# MRF49XA--0805_Mod.net
KiCad netlist of a schematic drawn in EAGLE
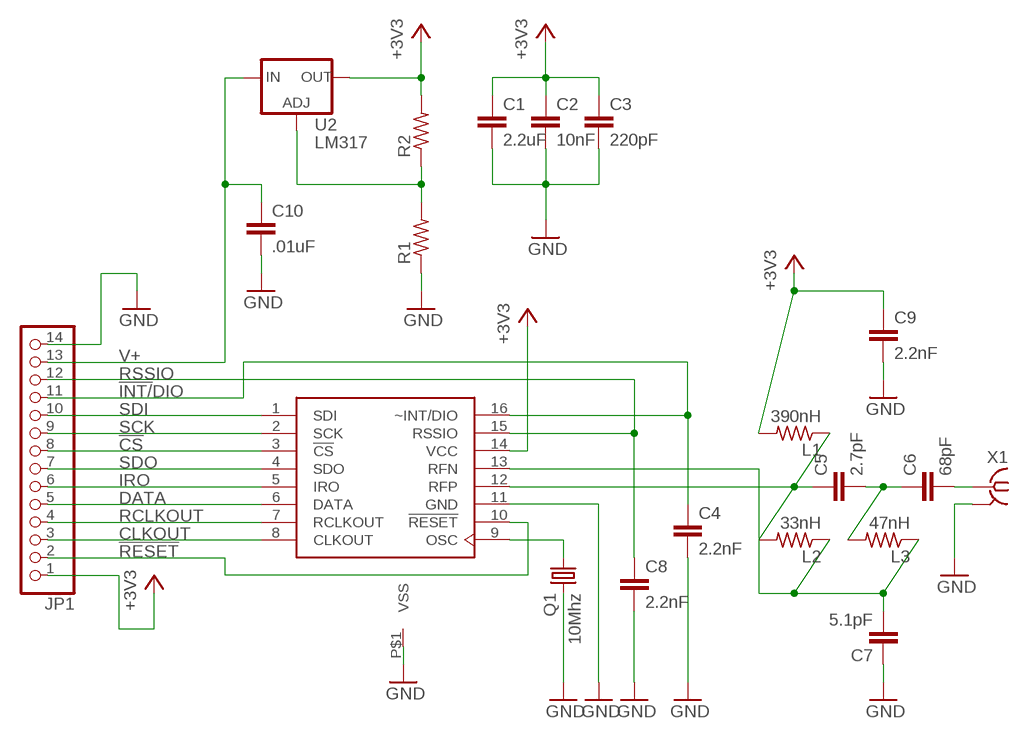
[diagram p0: schematic, sheet 1]

(export (version "E")
  (design (tool "Eeschema 10.0.6"))
  (components
    (comp (ref "C1")
      (value "2.2uF")
      (footprint "eagle-import:C0805")
      (libsource (lib "eagle-import") (part "C-EUC0805"))
    )
    (comp (ref "C2")
      (value "10nF")
      (footprint "eagle-import:C0805")
      (libsource (lib "eagle-import") (part "C-EUC0805"))
    )
    (comp (ref "C3")
      (value "220pF")
      (footprint "eagle-import:C0805")
      (libsource (lib "eagle-import") (part "C-EUC0805"))
    )
    (comp (ref "C4")
      (value "2.2nF")
      (footprint "eagle-import:C0805")
      (libsource (lib "eagle-import") (part "C-EUC0805"))
    )
    (comp (ref "C5")
      (value "2.7pF")
      (footprint "eagle-import:C0805")
      (libsource (lib "eagle-import") (part "C-EUC0805"))
    )
    (comp (ref "C6")
      (value "68pF")
      (footprint "eagle-import:C0805")
      (libsource (lib "eagle-import") (part "C-EUC0805"))
    )
    (comp (ref "C7")
      (value "5.1pF")
      (footprint "eagle-import:C0805")
      (libsource (lib "eagle-import") (part "C-EUC0805"))
    )
    (comp (ref "C8")
      (value "2.2nF")
      (footprint "eagle-import:C0805")
      (libsource (lib "eagle-import") (part "C-EUC0805"))
    )
    (comp (ref "C9")
      (value "2.2nF")
      (footprint "eagle-import:C0805")
      (libsource (lib "eagle-import") (part "C-EUC0805"))
    )
    (comp (ref "C10")
      (value ".01uF")
      (footprint "eagle-import:C0805")
      (libsource (lib "eagle-import") (part "C-EUC0805"))
    )
    (comp (ref "JP1")
      (value "PINHD-1X14")
      (footprint "eagle-import:1X14")
      (libsource (lib "eagle-import") (part "PINHD-1X14"))
    )
    (comp (ref "L1")
      (value "390nH")
      (footprint "eagle-import:R0805")
      (libsource (lib "eagle-import") (part "resistor_R-US_R0805"))
    )
    (comp (ref "L2")
      (value "33nH")
      (footprint "eagle-import:R0805")
      (libsource (lib "eagle-import") (part "resistor_R-US_R0805"))
    )
    (comp (ref "L3")
      (value "47nH")
      (footprint "eagle-import:R0805")
      (libsource (lib "eagle-import") (part "resistor_R-US_R0805"))
    )
    (comp (ref "Q1")
      (value "10Mhz")
      (footprint "eagle-import:CTS406")
      (libsource (lib "eagle-import") (part "CRYSTALCTS406"))
    )
    (comp (ref "R1")
      (value "R-US_M0805")
      (footprint "eagle-import:M0805")
      (libsource (lib "eagle-import") (part "R-US_M0805"))
    )
    (comp (ref "R2")
      (value "R-US_M0805")
      (footprint "eagle-import:M0805")
      (libsource (lib "eagle-import") (part "R-US_M0805"))
    )
    (comp (ref "U$1")
      (value "MRF49XA")
      (footprint "eagle-import:TSSOP16")
      (libsource (lib "eagle-import") (part "MRF49XA"))
    )
    (comp (ref "U2")
      (value "LM317")
      (footprint "eagle-import:SOT223")
      (libsource (lib "eagle-import") (part "V_REG_317SMD"))
    )
    (comp (ref "X1")
      (value "SMA-142-0701-871/876")
      (footprint "eagle-import:J502-ND-142-0701-871_876")
      (libsource (lib "eagle-import") (part "SMA-142-0701-871/876"))
    )
  )
  (nets
    (net (code "1") (name "+3V3") (class "Default")
      (node (ref "C1") (pin "1") (pinfunction "1_1") (pintype "passive"))
      (node (ref "C2") (pin "1") (pinfunction "1_1") (pintype "passive"))
      (node (ref "C3") (pin "1") (pinfunction "1_1") (pintype "passive"))
      (node (ref "C9") (pin "1") (pinfunction "1_1") (pintype "passive"))
      (node (ref "JP1") (pin "1") (pinfunction "1_1") (pintype "passive"))
      (node (ref "L1") (pin "2") (pinfunction "2_2") (pintype "passive"))
      (node (ref "R2") (pin "2") (pinfunction "2_2") (pintype "passive"))
      (node (ref "U$1") (pin "14") (pinfunction "VCC_14") (pintype "bidirectional"))
      (node (ref "U2") (pin "2") (pinfunction "OUT_2") (pintype "output"))
    )
    (net (code "2") (name "/CLKOUT") (class "Default")
      (node (ref "JP1") (pin "3") (pinfunction "3_3") (pintype "passive"))
      (node (ref "U$1") (pin "8") (pinfunction "CLKOUT_8") (pintype "output"))
    )
    (net (code "3") (name "/DATA") (class "Default")
      (node (ref "JP1") (pin "5") (pinfunction "5_5") (pintype "passive"))
      (node (ref "U$1") (pin "6") (pinfunction "DATA_6") (pintype "bidirectional"))
    )
    (net (code "4") (name "/IRO") (class "Default")
      (node (ref "JP1") (pin "6") (pinfunction "6_6") (pintype "passive"))
      (node (ref "U$1") (pin "5") (pinfunction "IRO_5") (pintype "output"))
    )
    (net (code "5") (name "/RCLKOUT") (class "Default")
      (node (ref "JP1") (pin "4") (pinfunction "4_4") (pintype "passive"))
      (node (ref "U$1") (pin "7") (pinfunction "RCLKOUT_7") (pintype "bidirectional"))
    )
    (net (code "6") (name "/RSSIO") (class "Default")
      (node (ref "C8") (pin "1") (pinfunction "1_1") (pintype "passive"))
      (node (ref "JP1") (pin "12") (pinfunction "12_12") (pintype "passive"))
      (node (ref "U$1") (pin "15") (pinfunction "RSSIO_15") (pintype "bidirectional"))
    )
    (net (code "7") (name "/SCK") (class "Default")
      (node (ref "JP1") (pin "9") (pinfunction "9_9") (pintype "passive"))
      (node (ref "U$1") (pin "2") (pinfunction "SCK_2") (pintype "input"))
    )
    (net (code "8") (name "/SDI") (class "Default")
      (node (ref "JP1") (pin "10") (pinfunction "10_10") (pintype "passive"))
      (node (ref "U$1") (pin "1") (pinfunction "SDI_1") (pintype "input"))
    )
    (net (code "9") (name "/SDO") (class "Default")
      (node (ref "JP1") (pin "7") (pinfunction "7_7") (pintype "passive"))
      (node (ref "U$1") (pin "4") (pinfunction "SDO_4") (pintype "output"))
    )
    (net (code "10") (name "/V+") (class "Default")
      (node (ref "C10") (pin "1") (pinfunction "1_1") (pintype "passive"))
      (node (ref "JP1") (pin "13") (pinfunction "13_13") (pintype "passive"))
      (node (ref "U2") (pin "3") (pinfunction "IN_3") (pintype "input"))
    )
    (net (code "11") (name "/~{CS}") (class "Default")
      (node (ref "JP1") (pin "8") (pinfunction "8_8") (pintype "passive"))
      (node (ref "U$1") (pin "3") (pinfunction "~{CS}_3") (pintype "input"))
    )
    (net (code "12") (name "/~{INT{slash}}DIO") (class "Default")
      (node (ref "C4") (pin "1") (pinfunction "1_1") (pintype "passive"))
      (node (ref "JP1") (pin "11") (pinfunction "11_11") (pintype "passive"))
      (node (ref "U$1") (pin "16") (pinfunction "~{INT/DIO}_16") (pintype "bidirectional"))
    )
    (net (code "13") (name "/~{RESET}") (class "Default")
      (node (ref "JP1") (pin "2") (pinfunction "2_2") (pintype "passive"))
      (node (ref "U$1") (pin "10") (pinfunction "~{RESET}_10") (pintype "bidirectional"))
    )
    (net (code "14") (name "GND") (class "Default")
      (node (ref "C1") (pin "2") (pinfunction "2_2") (pintype "passive"))
      (node (ref "C10") (pin "2") (pinfunction "2_2") (pintype "passive"))
      (node (ref "C2") (pin "2") (pinfunction "2_2") (pintype "passive"))
      (node (ref "C3") (pin "2") (pinfunction "2_2") (pintype "passive"))
      (node (ref "C4") (pin "2") (pinfunction "2_2") (pintype "passive"))
      (node (ref "C7") (pin "1") (pinfunction "1_1") (pintype "passive"))
      (node (ref "C8") (pin "2") (pinfunction "2_2") (pintype "passive"))
      (node (ref "C9") (pin "2") (pinfunction "2_2") (pintype "passive"))
      (node (ref "JP1") (pin "14") (pinfunction "14_14") (pintype "passive"))
      (node (ref "Q1") (pin "3") (pinfunction "2_3") (pintype "passive"))
      (node (ref "R1") (pin "1") (pinfunction "1_1") (pintype "passive"))
      (node (ref "U$1") (pin "11") (pinfunction "GND_11") (pintype "bidirectional"))
      (node (ref "U$1") (pin "P$1") (pinfunction "VSS_P$1") (pintype "power_in"))
      (node (ref "X1") (pin "G@1") (pinfunction "GND_G@1") (pintype "power_in"))
    )
    (net (code "15") (name "Net-(C5-Pad2)") (class "Default")
      (node (ref "C5") (pin "2") (pinfunction "2_2") (pintype "passive"))
      (node (ref "C6") (pin "1") (pinfunction "1_1") (pintype "passive"))
      (node (ref "L3") (pin "2") (pinfunction "2_2") (pintype "passive"))
    )
    (net (code "16") (name "Net-(C6-Pad2)") (class "Default")
      (node (ref "C6") (pin "2") (pinfunction "2_2") (pintype "passive"))
      (node (ref "X1") (pin "1") (pinfunction "1_1") (pintype "passive"))
    )
    (net (code "17") (name "Net-(U$1A-OSC)") (class "Default")
      (node (ref "Q1") (pin "1") (pinfunction "1_1") (pintype "passive"))
      (node (ref "U$1") (pin "9") (pinfunction "OSC_9") (pintype "bidirectional"))
    )
    (net (code "18") (name "Net-(U$1A-RFN)") (class "Default")
      (node (ref "C7") (pin "2") (pinfunction "2_2") (pintype "passive"))
      (node (ref "L2") (pin "1") (pinfunction "1_1") (pintype "passive"))
      (node (ref "L3") (pin "1") (pinfunction "1_1") (pintype "passive"))
      (node (ref "U$1") (pin "13") (pinfunction "RFN_13") (pintype "bidirectional"))
    )
    (net (code "19") (name "Net-(U$1A-RFP)") (class "Default")
      (node (ref "C5") (pin "1") (pinfunction "1_1") (pintype "passive"))
      (node (ref "L1") (pin "1") (pinfunction "1_1") (pintype "passive"))
      (node (ref "L2") (pin "2") (pinfunction "2_2") (pintype "passive"))
      (node (ref "U$1") (pin "12") (pinfunction "RFP_12") (pintype "bidirectional"))
    )
    (net (code "20") (name "Net-(U2-ADJ)") (class "Default")
      (node (ref "R1") (pin "2") (pinfunction "2_2") (pintype "passive"))
      (node (ref "R2") (pin "1") (pinfunction "1_1") (pintype "passive"))
      (node (ref "U2") (pin "1") (pinfunction "ADJ_1") (pintype "input"))
    )
  )
)
